# OpAmp-Inverting-3Transistor-alt3.net
KiCad netlist of a schematic drawn in EAGLE
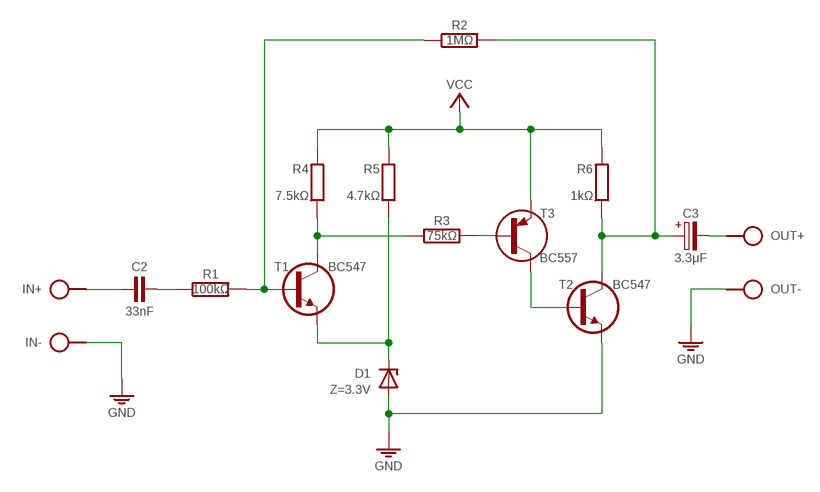
[diagram p0: schematic, sheet 1]

(export (version "E")
  (design (tool "Eeschema 10.0.6"))
  (components
    (comp (ref "C2")
      (value "33nF")
      (footprint "eagle-import:C050-020X044")
      (libsource (lib "eagle-import") (part "C050-020X044"))
    )
    (comp (ref "C3")
      (value "3.3μF")
      (footprint "eagle-import:E2.5-4_V")
      (libsource (lib "eagle-import") (part "CPOLE2,5-4/V"))
    )
    (comp (ref "D1")
      (value "Z=3.3V")
      (footprint "eagle-import:DO34Z2,5")
      (libsource (lib "eagle-import") (part "Z-DIODE34Z2,5"))
    )
    (comp (ref "IN")
      (value "SPAD+--+")
      (footprint "eagle-import:SPAD-+")
      (libsource (lib "eagle-import") (part "SPAD+--+"))
    )
    (comp (ref "J1")
      (value "VCC_GNDPWR-R")
      (footprint "eagle-import:PWR-R")
      (libsource (lib "eagle-import") (part "VCC_GNDPWR-R"))
    )
    (comp (ref "OUT")
      (value "SPAD+-+-")
      (footprint "eagle-import:SPAD+-")
      (libsource (lib "eagle-import") (part "SPAD+-+-"))
    )
    (comp (ref "R1")
      (value "100kΩ")
      (footprint "eagle-import:0204_10-V")
      (libsource (lib "eagle-import") (part "R-H0204/10-V"))
    )
    (comp (ref "R2")
      (value "1MΩ")
      (footprint "eagle-import:0204_10")
      (libsource (lib "eagle-import") (part "R-H0204/10"))
    )
    (comp (ref "R3")
      (value "75kΩ")
      (footprint "eagle-import:0204_10")
      (libsource (lib "eagle-import") (part "R-H0204/10"))
    )
    (comp (ref "R4")
      (value "7.5kΩ")
      (footprint "eagle-import:0204_10")
      (libsource (lib "eagle-import") (part "R0204/10"))
    )
    (comp (ref "R5")
      (value "4.7kΩ")
      (footprint "eagle-import:0204_10")
      (libsource (lib "eagle-import") (part "R0204/10"))
    )
    (comp (ref "R6")
      (value "1kΩ")
      (footprint "eagle-import:0204_10-V")
      (libsource (lib "eagle-import") (part "R0204/10-V"))
    )
    (comp (ref "T1")
      (value "BC547")
      (footprint "eagle-import:TO92-CBE")
      (libsource (lib "eagle-import") (part "BC547CBE"))
    )
    (comp (ref "T2")
      (value "BC547")
      (footprint "eagle-import:TO92-CBE")
      (libsource (lib "eagle-import") (part "BC547CBE"))
    )
    (comp (ref "T3")
      (value "BC557")
      (footprint "eagle-import:TO92-CBE")
      (libsource (lib "eagle-import") (part "BC557CBE"))
    )
  )
  (nets
    (net (code "1") (name "GND") (class "Default")
      (node (ref "D1") (pin "A") (pinfunction "A_A") (pintype "passive"))
      (node (ref "IN") (pin "1") (pinfunction "P$1_1") (pintype "passive"))
      (node (ref "J1") (pin "1") (pinfunction "GND_1") (pintype "power_in"))
      (node (ref "OUT") (pin "1") (pinfunction "P$1_1") (pintype "passive"))
      (node (ref "T2") (pin "E") (pinfunction "E_E") (pintype "passive"))
    )
    (net (code "2") (name "Net-(C2-Pad1)") (class "Default")
      (node (ref "C2") (pin "1") (pinfunction "1_1") (pintype "passive"))
      (node (ref "R1") (pin "1") (pinfunction "1_1") (pintype "passive"))
    )
    (net (code "3") (name "Net-(C3-Pad+)") (class "Default")
      (node (ref "C3") (pin "+") (pinfunction "+_+") (pintype "passive"))
      (node (ref "R2") (pin "2") (pinfunction "2_2") (pintype "passive"))
      (node (ref "R6") (pin "2") (pinfunction "2_2") (pintype "passive"))
      (node (ref "T2") (pin "C") (pinfunction "C_C") (pintype "passive"))
    )
    (net (code "4") (name "Net-(D1-PadC)") (class "Default")
      (node (ref "D1") (pin "C") (pinfunction "C_C") (pintype "passive"))
      (node (ref "R5") (pin "2") (pinfunction "2_2") (pintype "passive"))
      (node (ref "T1") (pin "E") (pinfunction "E_E") (pintype "passive"))
    )
    (net (code "5") (name "Net-(INA-P$1)") (class "Default")
      (node (ref "C2") (pin "2") (pinfunction "2_2") (pintype "passive"))
      (node (ref "IN") (pin "2") (pinfunction "P$1_2") (pintype "passive"))
    )
    (net (code "6") (name "Net-(J1A-VCC)") (class "Default")
      (node (ref "J1") (pin "2") (pinfunction "VCC_2") (pintype "power_in"))
      (node (ref "R4") (pin "1") (pinfunction "1_1") (pintype "passive"))
      (node (ref "R5") (pin "1") (pinfunction "1_1") (pintype "passive"))
      (node (ref "R6") (pin "1") (pinfunction "1_1") (pintype "passive"))
      (node (ref "T3") (pin "E") (pinfunction "E_E") (pintype "passive"))
    )
    (net (code "7") (name "Net-(OUTA-P$1)") (class "Default")
      (node (ref "C3") (pin "-") (pinfunction "-_-") (pintype "passive"))
      (node (ref "OUT") (pin "2") (pinfunction "P$1_2") (pintype "passive"))
    )
    (net (code "8") (name "Net-(R1-Pad2)") (class "Default")
      (node (ref "R1") (pin "2") (pinfunction "2_2") (pintype "passive"))
      (node (ref "R2") (pin "1") (pinfunction "1_1") (pintype "passive"))
      (node (ref "T1") (pin "B") (pinfunction "B_B") (pintype "passive"))
    )
    (net (code "9") (name "Net-(R3-Pad1)") (class "Default")
      (node (ref "R3") (pin "1") (pinfunction "1_1") (pintype "passive"))
      (node (ref "R4") (pin "2") (pinfunction "2_2") (pintype "passive"))
      (node (ref "T1") (pin "C") (pinfunction "C_C") (pintype "passive"))
    )
    (net (code "10") (name "Net-(R3-Pad2)") (class "Default")
      (node (ref "R3") (pin "2") (pinfunction "2_2") (pintype "passive"))
      (node (ref "T3") (pin "B") (pinfunction "B_B") (pintype "passive"))
    )
    (net (code "11") (name "Net-(T2-PadB)") (class "Default")
      (node (ref "T2") (pin "B") (pinfunction "B_B") (pintype "passive"))
      (node (ref "T3") (pin "C") (pinfunction "C_C") (pintype "passive"))
    )
  )
)
